# untitled.net
KiCad netlist of a schematic drawn in EAGLE
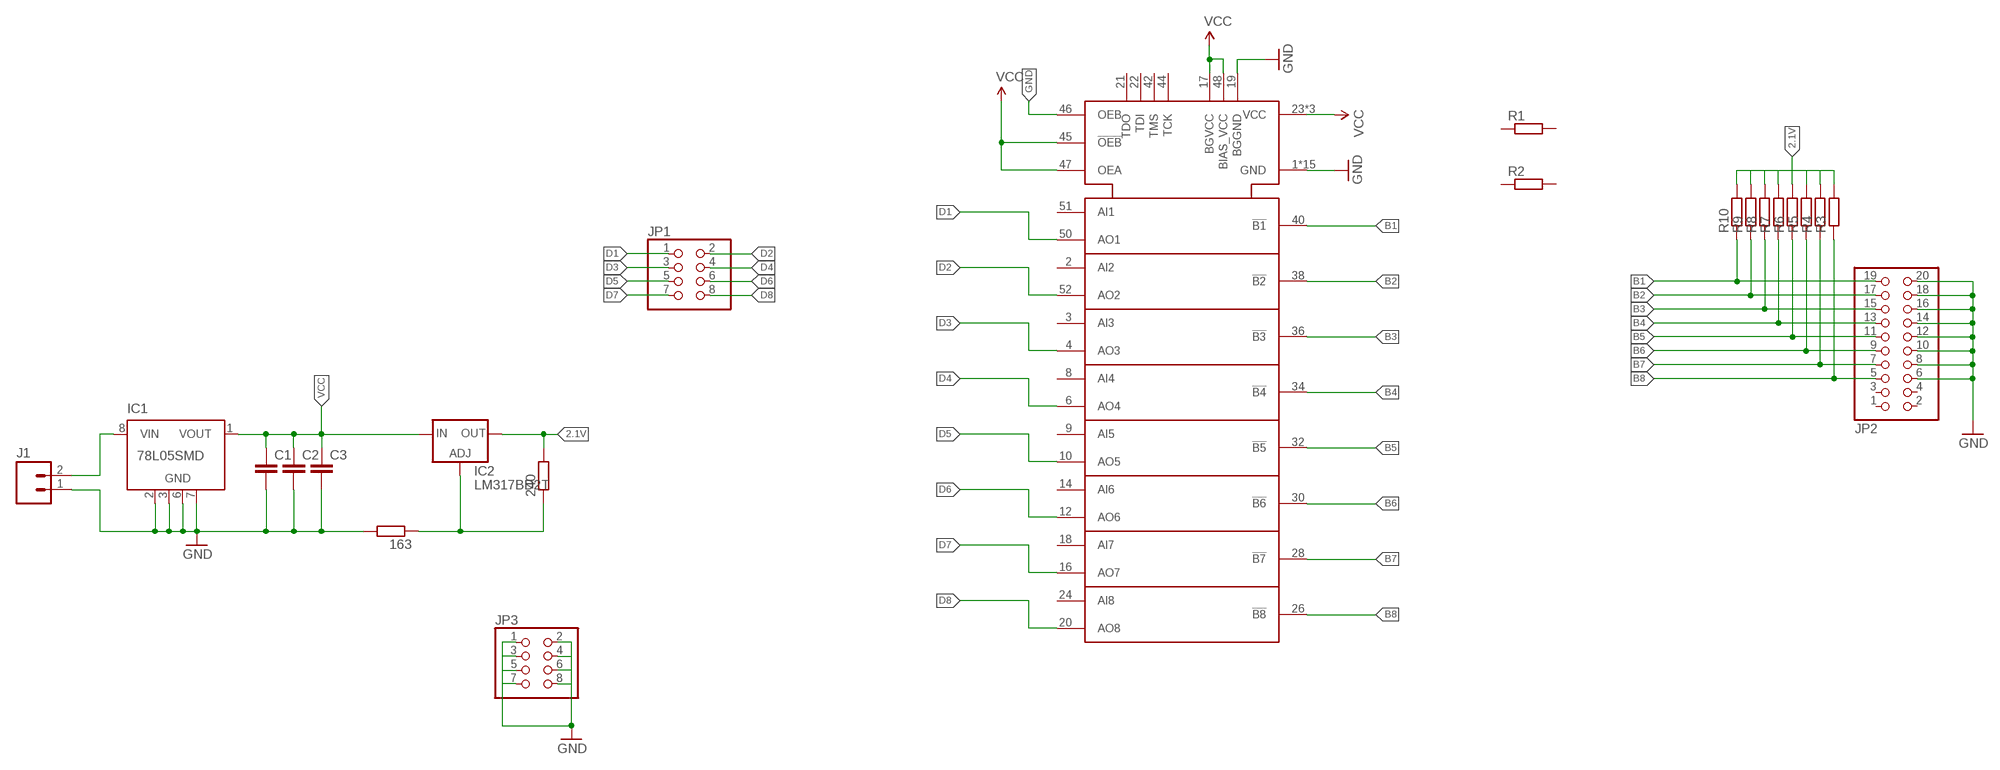
[diagram p0: schematic, sheet 1]

(export (version "E")
  (design (tool "Eeschema 10.0.6"))
  (components
    (comp (ref "163")
      (value "R0805")
      (footprint "eagle-import:R0805")
      (libsource (lib "eagle-import") (part "R0805"))
    )
    (comp (ref "240")
      (value "R0805")
      (footprint "eagle-import:R0805")
      (libsource (lib "eagle-import") (part "R0805"))
    )
    (comp (ref "C1")
      (value "CC0805")
      (footprint "eagle-import:C0805")
      (libsource (lib "eagle-import") (part "CC0805"))
    )
    (comp (ref "C2")
      (value "CC0805")
      (footprint "eagle-import:C0805")
      (libsource (lib "eagle-import") (part "CC0805"))
    )
    (comp (ref "C3")
      (value "CC0805")
      (footprint "eagle-import:C0805")
      (libsource (lib "eagle-import") (part "CC0805"))
    )
    (comp (ref "IC1")
      (value "78L05SMD")
      (footprint "eagle-import:SO08")
      (libsource (lib "eagle-import") (part "78LSMD05"))
    )
    (comp (ref "IC2")
      (value "LM317BD2T")
      (footprint "eagle-import:D2PACK")
      (libsource (lib "eagle-import") (part "LM317?BD2T"))
    )
    (comp (ref "J1")
      (value "M02LOCK_LONGPADS")
      (footprint "eagle-import:1X02_LOCK_LONGPADS")
      (libsource (lib "eagle-import") (part "M02LOCK_LONGPADS"))
    )
    (comp (ref "JP1")
      (value "PINHD-2X04_2.54-SMD")
      (footprint "eagle-import:2X04SMD")
      (libsource (lib "eagle-import") (part "PINHD-2X04_2.54-SMD"))
    )
    (comp (ref "JP2")
      (value "PINHD-2X10_2.54-SMD")
      (footprint "eagle-import:2X10SMD")
      (libsource (lib "eagle-import") (part "PINHD-2X10_2.54-SMD"))
    )
    (comp (ref "JP3")
      (value "PINHD-2X04_2.54-SMD")
      (footprint "eagle-import:2X04SMD")
      (libsource (lib "eagle-import") (part "PINHD-2X04_2.54-SMD"))
    )
    (comp (ref "R1")
      (value "R0805")
      (footprint "eagle-import:R0805")
      (libsource (lib "eagle-import") (part "R0805"))
    )
    (comp (ref "R2")
      (value "R0805")
      (footprint "eagle-import:R0805")
      (libsource (lib "eagle-import") (part "R0805"))
    )
    (comp (ref "R3")
      (value "R0805")
      (footprint "eagle-import:R0805")
      (libsource (lib "eagle-import") (part "R0805"))
    )
    (comp (ref "R4")
      (value "R0805")
      (footprint "eagle-import:R0805")
      (libsource (lib "eagle-import") (part "R0805"))
    )
    (comp (ref "R5")
      (value "R0805")
      (footprint "eagle-import:R0805")
      (libsource (lib "eagle-import") (part "R0805"))
    )
    (comp (ref "R6")
      (value "R0805")
      (footprint "eagle-import:R0805")
      (libsource (lib "eagle-import") (part "R0805"))
    )
    (comp (ref "R7")
      (value "R0805")
      (footprint "eagle-import:R0805")
      (libsource (lib "eagle-import") (part "R0805"))
    )
    (comp (ref "R8")
      (value "R0805")
      (footprint "eagle-import:R0805")
      (libsource (lib "eagle-import") (part "R0805"))
    )
    (comp (ref "R9")
      (value "R0805")
      (footprint "eagle-import:R0805")
      (libsource (lib "eagle-import") (part "R0805"))
    )
    (comp (ref "R10")
      (value "R0805")
      (footprint "eagle-import:R0805")
      (libsource (lib "eagle-import") (part "R0805"))
    )
    (comp (ref "U$1")
      (value "SN74FB2050")
      (footprint "eagle-import:TQFP-10X10-52")
      (libsource (lib "eagle-import") (part "SN74FB2050"))
    )
  )
  (nets
    (net (code "1") (name "2.1V") (class "Default")
      (node (ref "240") (pin "2") (pinfunction "2_2") (pintype "passive"))
      (node (ref "IC2") (pin "2") (pinfunction "OUT_2") (pintype "passive"))
      (node (ref "R10") (pin "2") (pinfunction "2_2") (pintype "passive"))
      (node (ref "R3") (pin "2") (pinfunction "2_2") (pintype "passive"))
      (node (ref "R4") (pin "2") (pinfunction "2_2") (pintype "passive"))
      (node (ref "R5") (pin "2") (pinfunction "2_2") (pintype "passive"))
      (node (ref "R6") (pin "2") (pinfunction "2_2") (pintype "passive"))
      (node (ref "R7") (pin "2") (pinfunction "2_2") (pintype "passive"))
      (node (ref "R8") (pin "2") (pinfunction "2_2") (pintype "passive"))
      (node (ref "R9") (pin "2") (pinfunction "2_2") (pintype "passive"))
    )
    (net (code "2") (name "B1") (class "Default")
      (node (ref "JP2") (pin "19") (pinfunction "19_19") (pintype "passive"))
      (node (ref "R10") (pin "1") (pinfunction "1_1") (pintype "passive"))
      (node (ref "U$1") (pin "40") (pinfunction "~{B1}_40") (pintype "bidirectional"))
    )
    (net (code "3") (name "B2") (class "Default")
      (node (ref "JP2") (pin "17") (pinfunction "17_17") (pintype "passive"))
      (node (ref "R9") (pin "1") (pinfunction "1_1") (pintype "passive"))
      (node (ref "U$1") (pin "38") (pinfunction "~{B2}_38") (pintype "bidirectional"))
    )
    (net (code "4") (name "B3") (class "Default")
      (node (ref "JP2") (pin "15") (pinfunction "15_15") (pintype "passive"))
      (node (ref "R8") (pin "1") (pinfunction "1_1") (pintype "passive"))
      (node (ref "U$1") (pin "36") (pinfunction "~{B3}_36") (pintype "bidirectional"))
    )
    (net (code "5") (name "B4") (class "Default")
      (node (ref "JP2") (pin "13") (pinfunction "13_13") (pintype "passive"))
      (node (ref "R7") (pin "1") (pinfunction "1_1") (pintype "passive"))
      (node (ref "U$1") (pin "34") (pinfunction "~{B4}_34") (pintype "bidirectional"))
    )
    (net (code "6") (name "B5") (class "Default")
      (node (ref "JP2") (pin "11") (pinfunction "11_11") (pintype "passive"))
      (node (ref "R6") (pin "1") (pinfunction "1_1") (pintype "passive"))
      (node (ref "U$1") (pin "32") (pinfunction "~{B5}_32") (pintype "bidirectional"))
    )
    (net (code "7") (name "B6") (class "Default")
      (node (ref "JP2") (pin "9") (pinfunction "9_9") (pintype "passive"))
      (node (ref "R5") (pin "1") (pinfunction "1_1") (pintype "passive"))
      (node (ref "U$1") (pin "30") (pinfunction "~{B6}_30") (pintype "bidirectional"))
    )
    (net (code "8") (name "B7") (class "Default")
      (node (ref "JP2") (pin "7") (pinfunction "7_7") (pintype "passive"))
      (node (ref "R4") (pin "1") (pinfunction "1_1") (pintype "passive"))
      (node (ref "U$1") (pin "28") (pinfunction "~{B7}_28") (pintype "bidirectional"))
    )
    (net (code "9") (name "B8") (class "Default")
      (node (ref "JP2") (pin "5") (pinfunction "5_5") (pintype "passive"))
      (node (ref "R3") (pin "1") (pinfunction "1_1") (pintype "passive"))
      (node (ref "U$1") (pin "26") (pinfunction "~{B8}_26") (pintype "bidirectional"))
    )
    (net (code "10") (name "D1") (class "Default")
      (node (ref "JP1") (pin "1") (pinfunction "1_1") (pintype "passive"))
      (node (ref "U$1") (pin "50") (pinfunction "AO1_50") (pintype "bidirectional"))
    )
    (net (code "11") (name "D2") (class "Default")
      (node (ref "JP1") (pin "2") (pinfunction "2_2") (pintype "passive"))
      (node (ref "U$1") (pin "52") (pinfunction "AO2_52") (pintype "bidirectional"))
    )
    (net (code "12") (name "D3") (class "Default")
      (node (ref "JP1") (pin "3") (pinfunction "3_3") (pintype "passive"))
      (node (ref "U$1") (pin "4") (pinfunction "AO3_4") (pintype "bidirectional"))
    )
    (net (code "13") (name "D4") (class "Default")
      (node (ref "JP1") (pin "4") (pinfunction "4_4") (pintype "passive"))
      (node (ref "U$1") (pin "6") (pinfunction "AO4_6") (pintype "bidirectional"))
    )
    (net (code "14") (name "D5") (class "Default")
      (node (ref "JP1") (pin "5") (pinfunction "5_5") (pintype "passive"))
      (node (ref "U$1") (pin "10") (pinfunction "AO5_10") (pintype "bidirectional"))
    )
    (net (code "15") (name "D6") (class "Default")
      (node (ref "JP1") (pin "6") (pinfunction "6_6") (pintype "passive"))
      (node (ref "U$1") (pin "12") (pinfunction "AO6_12") (pintype "bidirectional"))
    )
    (net (code "16") (name "D7") (class "Default")
      (node (ref "JP1") (pin "7") (pinfunction "7_7") (pintype "passive"))
      (node (ref "U$1") (pin "16") (pinfunction "AO7_16") (pintype "bidirectional"))
    )
    (net (code "17") (name "D8") (class "Default")
      (node (ref "JP1") (pin "8") (pinfunction "8_8") (pintype "passive"))
      (node (ref "U$1") (pin "20") (pinfunction "AO8_20") (pintype "bidirectional"))
    )
    (net (code "18") (name "GND") (class "Default")
      (node (ref "163") (pin "2") (pinfunction "2_2") (pintype "passive"))
      (node (ref "C1") (pin "2") (pinfunction "2_2") (pintype "passive"))
      (node (ref "C2") (pin "2") (pinfunction "2_2") (pintype "passive"))
      (node (ref "C3") (pin "2") (pinfunction "2_2") (pintype "passive"))
      (node (ref "IC1") (pin "2") (pinfunction "GND_2") (pintype "power_in"))
      (node (ref "IC1") (pin "3") (pinfunction "GND_3") (pintype "power_in"))
      (node (ref "IC1") (pin "6") (pinfunction "GND_6") (pintype "power_in"))
      (node (ref "IC1") (pin "7") (pinfunction "GND_7") (pintype "power_in"))
      (node (ref "J1") (pin "1") (pinfunction "1_1") (pintype "passive"))
      (node (ref "JP2") (pin "10") (pinfunction "10_10") (pintype "passive"))
      (node (ref "JP2") (pin "12") (pinfunction "12_12") (pintype "passive"))
      (node (ref "JP2") (pin "14") (pinfunction "14_14") (pintype "passive"))
      (node (ref "JP2") (pin "16") (pinfunction "16_16") (pintype "passive"))
      (node (ref "JP2") (pin "18") (pinfunction "18_18") (pintype "passive"))
      (node (ref "JP2") (pin "20") (pinfunction "20_20") (pintype "passive"))
      (node (ref "JP2") (pin "6") (pinfunction "6_6") (pintype "passive"))
      (node (ref "JP2") (pin "8") (pinfunction "8_8") (pintype "passive"))
      (node (ref "JP3") (pin "1") (pinfunction "1_1") (pintype "passive"))
      (node (ref "JP3") (pin "2") (pinfunction "2_2") (pintype "passive"))
      (node (ref "JP3") (pin "3") (pinfunction "3_3") (pintype "passive"))
      (node (ref "JP3") (pin "4") (pinfunction "4_4") (pintype "passive"))
      (node (ref "JP3") (pin "5") (pinfunction "5_5") (pintype "passive"))
      (node (ref "JP3") (pin "6") (pinfunction "6_6") (pintype "passive"))
      (node (ref "JP3") (pin "7") (pinfunction "7_7") (pintype "passive"))
      (node (ref "JP3") (pin "8") (pinfunction "8_8") (pintype "passive"))
      (node (ref "U$1") (pin "1") (pinfunction "GND_1") (pintype "bidirectional"))
      (node (ref "U$1") (pin "11") (pinfunction "GND_11") (pintype "bidirectional"))
      (node (ref "U$1") (pin "13") (pinfunction "GND_13") (pintype "bidirectional"))
      (node (ref "U$1") (pin "15") (pinfunction "GND_15") (pintype "bidirectional"))
      (node (ref "U$1") (pin "19") (pinfunction "BGGND_19") (pintype "bidirectional"))
      (node (ref "U$1") (pin "25") (pinfunction "GND_25") (pintype "bidirectional"))
      (node (ref "U$1") (pin "27") (pinfunction "GND_27") (pintype "bidirectional"))
      (node (ref "U$1") (pin "29") (pinfunction "GND_29") (pintype "bidirectional"))
      (node (ref "U$1") (pin "31") (pinfunction "GND_31") (pintype "bidirectional"))
      (node (ref "U$1") (pin "33") (pinfunction "GND_33") (pintype "bidirectional"))
      (node (ref "U$1") (pin "35") (pinfunction "GND_35") (pintype "bidirectional"))
      (node (ref "U$1") (pin "37") (pinfunction "GND_37") (pintype "bidirectional"))
      (node (ref "U$1") (pin "39") (pinfunction "GND_39") (pintype "bidirectional"))
      (node (ref "U$1") (pin "41") (pinfunction "GND_41") (pintype "bidirectional"))
      (node (ref "U$1") (pin "46") (pinfunction "OEB_46") (pintype "bidirectional"))
      (node (ref "U$1") (pin "5") (pinfunction "GND_5") (pintype "bidirectional"))
      (node (ref "U$1") (pin "7") (pinfunction "GND_7") (pintype "bidirectional"))
    )
    (net (code "19") (name "Net-(IC1A-VIN)") (class "Default")
      (node (ref "IC1") (pin "8") (pinfunction "VIN_8") (pintype "passive"))
      (node (ref "J1") (pin "2") (pinfunction "2_2") (pintype "passive"))
    )
    (net (code "20") (name "Net-(IC2-ADJ)") (class "Default")
      (node (ref "163") (pin "1") (pinfunction "1_1") (pintype "passive"))
      (node (ref "240") (pin "1") (pinfunction "1_1") (pintype "passive"))
      (node (ref "IC2") (pin "1") (pinfunction "ADJ_1") (pintype "input"))
    )
    (net (code "21") (name "VCC") (class "Default")
      (node (ref "C1") (pin "1") (pinfunction "1_1") (pintype "passive"))
      (node (ref "C2") (pin "1") (pinfunction "1_1") (pintype "passive"))
      (node (ref "C3") (pin "1") (pinfunction "1_1") (pintype "passive"))
      (node (ref "IC1") (pin "1") (pinfunction "VOUT_1") (pintype "output"))
      (node (ref "IC2") (pin "3") (pinfunction "IN_3") (pintype "input"))
      (node (ref "U$1") (pin "17") (pinfunction "BGVCC_17") (pintype "bidirectional"))
      (node (ref "U$1") (pin "23") (pinfunction "VCC_23") (pintype "bidirectional"))
      (node (ref "U$1") (pin "43") (pinfunction "VCC_43") (pintype "bidirectional"))
      (node (ref "U$1") (pin "45") (pinfunction "~{OEB}_45") (pintype "bidirectional"))
      (node (ref "U$1") (pin "47") (pinfunction "OEA_47") (pintype "bidirectional"))
      (node (ref "U$1") (pin "48") (pinfunction "BIAS_VCC_48") (pintype "bidirectional"))
      (node (ref "U$1") (pin "49") (pinfunction "VCC_49") (pintype "bidirectional"))
    )
    (net (code "22") (name "unconnected-(JP2-Pad1)") (class "Default")
      (node (ref "JP2") (pin "1") (pinfunction "1_1") (pintype "passive"))
    )
    (net (code "23") (name "unconnected-(JP2-Pad2)") (class "Default")
      (node (ref "JP2") (pin "2") (pinfunction "2_2") (pintype "passive"))
    )
    (net (code "24") (name "unconnected-(JP2-Pad3)") (class "Default")
      (node (ref "JP2") (pin "3") (pinfunction "3_3") (pintype "passive"))
    )
    (net (code "25") (name "unconnected-(JP2-Pad4)") (class "Default")
      (node (ref "JP2") (pin "4") (pinfunction "4_4") (pintype "passive"))
    )
    (net (code "26") (name "unconnected-(R1-Pad1)") (class "Default")
      (node (ref "R1") (pin "1") (pinfunction "1_1") (pintype "passive"))
    )
    (net (code "27") (name "unconnected-(R1-Pad2)") (class "Default")
      (node (ref "R1") (pin "2") (pinfunction "2_2") (pintype "passive"))
    )
    (net (code "28") (name "unconnected-(R2-Pad1)") (class "Default")
      (node (ref "R2") (pin "1") (pinfunction "1_1") (pintype "passive"))
    )
    (net (code "29") (name "unconnected-(R2-Pad2)") (class "Default")
      (node (ref "R2") (pin "2") (pinfunction "2_2") (pintype "passive"))
    )
    (net (code "30") (name "unconnected-(U$1-AI1-Pad51)") (class "Default")
      (node (ref "U$1") (pin "51") (pinfunction "AI1_51") (pintype "bidirectional"))
    )
    (net (code "31") (name "unconnected-(U$1-AI2-Pad2)") (class "Default")
      (node (ref "U$1") (pin "2") (pinfunction "AI2_2") (pintype "bidirectional"))
    )
    (net (code "32") (name "unconnected-(U$1-AI3-Pad3)") (class "Default")
      (node (ref "U$1") (pin "3") (pinfunction "AI3_3") (pintype "bidirectional"))
    )
    (net (code "33") (name "unconnected-(U$1-AI4-Pad8)") (class "Default")
      (node (ref "U$1") (pin "8") (pinfunction "AI4_8") (pintype "bidirectional"))
    )
    (net (code "34") (name "unconnected-(U$1-AI5-Pad9)") (class "Default")
      (node (ref "U$1") (pin "9") (pinfunction "AI5_9") (pintype "bidirectional"))
    )
    (net (code "35") (name "unconnected-(U$1-AI6-Pad14)") (class "Default")
      (node (ref "U$1") (pin "14") (pinfunction "AI6_14") (pintype "bidirectional"))
    )
    (net (code "36") (name "unconnected-(U$1-AI7-Pad18)") (class "Default")
      (node (ref "U$1") (pin "18") (pinfunction "AI7_18") (pintype "bidirectional"))
    )
    (net (code "37") (name "unconnected-(U$1-AI8-Pad24)") (class "Default")
      (node (ref "U$1") (pin "24") (pinfunction "AI8_24") (pintype "bidirectional"))
    )
    (net (code "38") (name "unconnected-(U$1-TCK-Pad44)") (class "Default")
      (node (ref "U$1") (pin "44") (pinfunction "TCK_44") (pintype "bidirectional"))
    )
    (net (code "39") (name "unconnected-(U$1-TDI-Pad22)") (class "Default")
      (node (ref "U$1") (pin "22") (pinfunction "TDI_22") (pintype "bidirectional"))
    )
    (net (code "40") (name "unconnected-(U$1-TDO-Pad21)") (class "Default")
      (node (ref "U$1") (pin "21") (pinfunction "TDO_21") (pintype "bidirectional"))
    )
    (net (code "41") (name "unconnected-(U$1-TMS-Pad42)") (class "Default")
      (node (ref "U$1") (pin "42") (pinfunction "TMS_42") (pintype "bidirectional"))
    )
  )
)
